# UD3c_bootstrap_output.net
KiCad netlist of a schematic drawn in Altium Designer
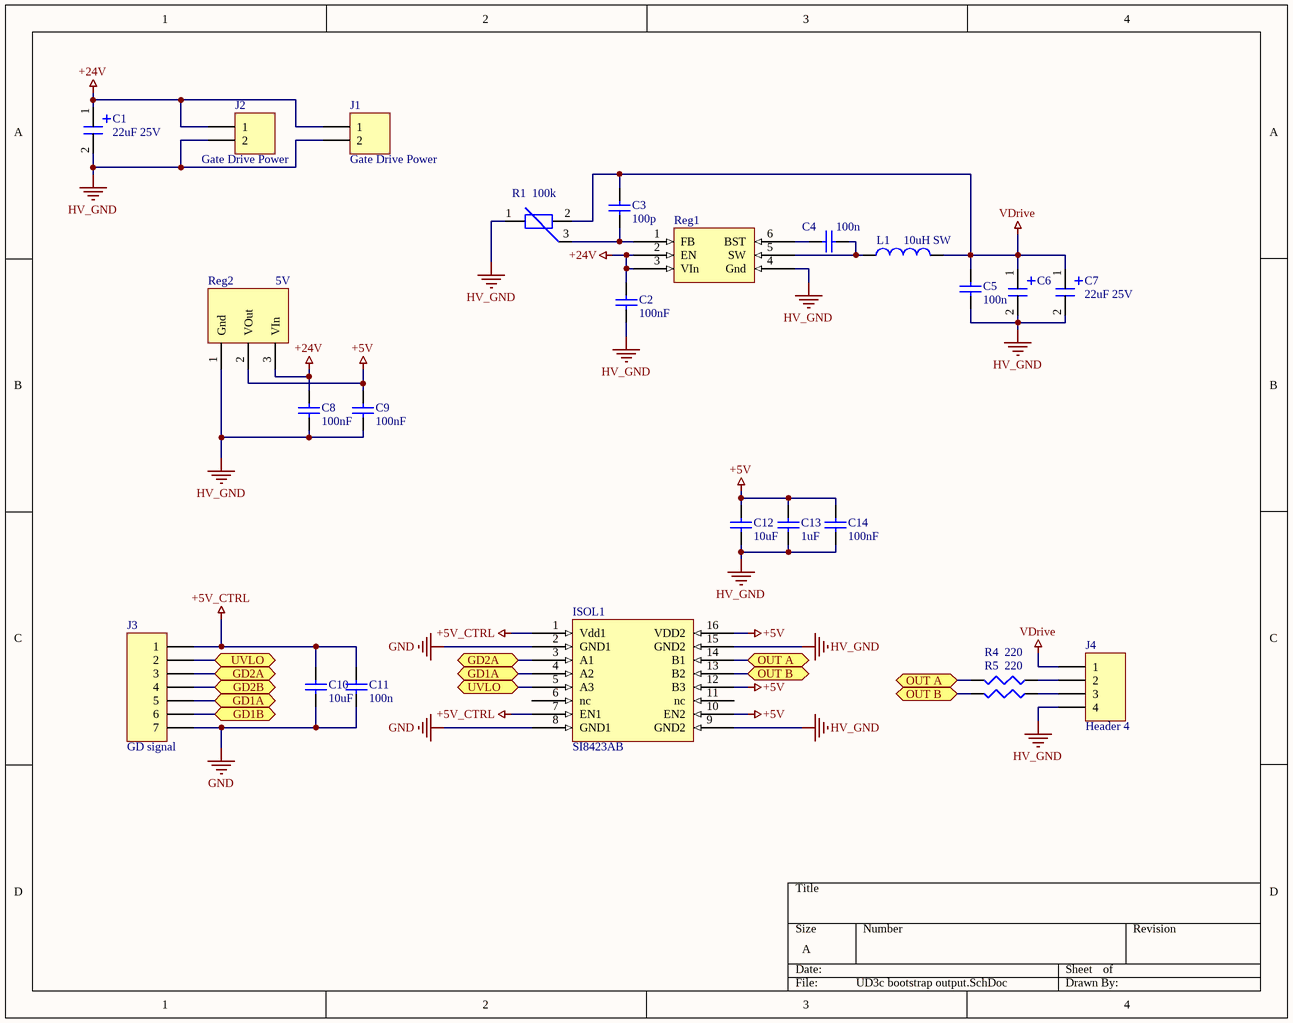
[diagram p0: UD3c bootstrap output.SchDoc]

(export (version "E")
  (design (tool "Eeschema 10.0.6"))
  (components
    (comp (ref "C1")
      (value "22uF 25V")
      (footprint "2917 Tantalum")
      (libsource (lib "stdLib") (part "Cap Polar"))
    )
    (comp (ref "C2") (value "100nF") (footprint "0603") (libsource (lib "stdLib") (part "Cap")))
    (comp (ref "C3") (value "100p") (footprint "0603") (libsource (lib "stdLib") (part "Cap")))
    (comp (ref "C4") (value "100n") (footprint "0603") (libsource (lib "stdLib") (part "Cap")))
    (comp (ref "C5") (value "100n") (footprint "0603") (libsource (lib "stdLib") (part "Cap")))
    (comp (ref "C6")
      (value "22uF 25V")
      (footprint "2917 Tantalum")
      (libsource (lib "stdLib") (part "Cap Polar"))
    )
    (comp (ref "C7")
      (value "22uF 25V")
      (footprint "2917 Tantalum")
      (libsource (lib "stdLib") (part "Cap Polar"))
    )
    (comp (ref "C8") (value "100nF") (footprint "0603") (libsource (lib "stdLib") (part "Cap")))
    (comp (ref "C9") (value "100nF") (footprint "0603") (libsource (lib "stdLib") (part "Cap")))
    (comp (ref "C10") (value "10uF") (footprint "0603") (libsource (lib "stdLib") (part "Cap")))
    (comp (ref "C11") (value "100n") (footprint "0603") (libsource (lib "stdLib") (part "Cap")))
    (comp (ref "C12") (value "10uF") (footprint "0603") (libsource (lib "stdLib") (part "Cap")))
    (comp (ref "C13") (value "1uF") (footprint "0603") (libsource (lib "stdLib") (part "Cap")))
    (comp (ref "C14") (value "100nF") (footprint "0603") (libsource (lib "stdLib") (part "Cap")))
    (comp (ref "ISOL1")
      (value "SI8423AB")
      (footprint "SOIC16 WIDE Isol")
      (description "Three (2/1) channel isolator")
      (libsource (lib "stdLib") (part "SI8423AB"))
    )
    (comp (ref "J1")
      (value "Gate Drive Power")
      (footprint "HDR1X2")
      (description "Header, 2-Pin")
      (fields (field (name "PUBLISHER") "Altium Limited"))
      (libsource (lib "Miscellaneous Connectors") (part "Header 2"))
    )
    (comp (ref "J2")
      (value "Gate Drive Power")
      (footprint "HDR1X2")
      (description "Header, 2-Pin")
      (fields (field (name "PUBLISHER") "Altium Limited"))
      (libsource (lib "Miscellaneous Connectors") (part "Header 2"))
    )
    (comp (ref "J3")
      (value "GD signal")
      (footprint "HDR1X7")
      (description "Header, 7-Pin")
      (fields (field (name "PUBLISHER") "Altium Limited"))
      (libsource (lib "Miscellaneous Connectors") (part "Header 7"))
    )
    (comp (ref "J4")
      (value "Header 4")
      (footprint "HDR1X4")
      (description "Header, 4-Pin")
      (fields (field (name "PUBLISHER") "Altium Limited"))
      (libsource (lib "Miscellaneous Connectors") (part "Header 4"))
    )
    (comp (ref "L1") (value "10uH SW") (footprint "1008") (libsource (lib "stdLib") (part "Inductor")))
    (comp (ref "R1") (value "100k") (footprint "Trimmer vert") (libsource (lib "stdLib") (part "Trimmer")))
    (comp (ref "R4") (value "220") (footprint "0603") (libsource (lib "stdLib") (part "Resistor")))
    (comp (ref "R5") (value "220") (footprint "0603") (libsource (lib "stdLib") (part "Resistor")))
    (comp (ref "Reg1")
      (value "Buck regulator")
      (footprint "TSOT26")
      (libsource (lib "stdLib") (part "AP6320"))
    )
    (comp (ref "Reg2") (value "5V") (footprint "SOT223") (libsource (lib "stdLib") (part "VReg")))
  )
  (nets
    (net (code "1") (name "+5V") (class "Default")
      (node (ref "C12") (pin "2") (pinfunction "2_2") (pintype "passive"))
      (node (ref "C13") (pin "2") (pinfunction "2_2") (pintype "passive"))
      (node (ref "C14") (pin "2") (pinfunction "2_2") (pintype "passive"))
      (node (ref "C9") (pin "2") (pinfunction "2_2") (pintype "passive"))
      (node (ref "ISOL1") (pin "10") (pinfunction "EN2_10") (pintype "input"))
      (node (ref "ISOL1") (pin "12") (pinfunction "B3_12") (pintype "input"))
      (node (ref "ISOL1") (pin "16") (pinfunction "VDD2_16") (pintype "input"))
      (node (ref "Reg2") (pin "2") (pinfunction "VOut_2") (pintype "passive"))
    )
    (net (code "2") (name "+5V_CTRL") (class "Default")
      (node (ref "C10") (pin "1") (pinfunction "1_1") (pintype "passive"))
      (node (ref "C11") (pin "1") (pinfunction "1_1") (pintype "passive"))
      (node (ref "ISOL1") (pin "1") (pinfunction "Vdd1_1") (pintype "input"))
      (node (ref "ISOL1") (pin "7") (pinfunction "EN1_7") (pintype "input"))
      (node (ref "J3") (pin "1") (pinfunction "1_1") (pintype "passive"))
    )
    (net (code "3") (name "+24V") (class "Default")
      (node (ref "C1") (pin "1") (pintype "passive"))
      (node (ref "C2") (pin "2") (pinfunction "2_2") (pintype "passive"))
      (node (ref "C8") (pin "2") (pinfunction "2_2") (pintype "passive"))
      (node (ref "J1") (pin "1") (pinfunction "1_1") (pintype "passive"))
      (node (ref "J2") (pin "1") (pinfunction "1_1") (pintype "passive"))
      (node (ref "Reg1") (pin "2") (pinfunction "EN_2") (pintype "input"))
      (node (ref "Reg1") (pin "3") (pinfunction "VIn_3") (pintype "input"))
      (node (ref "Reg2") (pin "3") (pinfunction "VIn_3") (pintype "passive"))
    )
    (net (code "4") (name "/GD1A") (class "Default")
      (node (ref "ISOL1") (pin "4") (pinfunction "A2_4") (pintype "input"))
      (node (ref "J3") (pin "5") (pinfunction "5_5") (pintype "passive"))
    )
    (net (code "5") (name "/GD1B") (class "Default")
      (node (ref "J3") (pin "6") (pinfunction "6_6") (pintype "passive"))
    )
    (net (code "6") (name "/GD2A") (class "Default")
      (node (ref "ISOL1") (pin "3") (pinfunction "A1_3") (pintype "input"))
      (node (ref "J3") (pin "3") (pinfunction "3_3") (pintype "passive"))
    )
    (net (code "7") (name "/GD2B") (class "Default")
      (node (ref "J3") (pin "4") (pinfunction "4_4") (pintype "passive"))
    )
    (net (code "8") (name "/OUT A") (class "Default")
      (node (ref "ISOL1") (pin "14") (pinfunction "B1_14") (pintype "input"))
      (node (ref "R4") (pin "2") (pinfunction "2_2") (pintype "passive"))
    )
    (net (code "9") (name "/OUT B") (class "Default")
      (node (ref "ISOL1") (pin "13") (pinfunction "B2_13") (pintype "input"))
      (node (ref "R5") (pin "2") (pinfunction "2_2") (pintype "passive"))
    )
    (net (code "10") (name "/UVLO") (class "Default")
      (node (ref "ISOL1") (pin "5") (pinfunction "A3_5") (pintype "input"))
      (node (ref "J3") (pin "2") (pinfunction "2_2") (pintype "passive"))
    )
    (net (code "11") (name "GND") (class "Default")
      (node (ref "C10") (pin "2") (pinfunction "2_2") (pintype "passive"))
      (node (ref "C11") (pin "2") (pinfunction "2_2") (pintype "passive"))
      (node (ref "ISOL1") (pin "2") (pinfunction "GND1_2") (pintype "input"))
      (node (ref "ISOL1") (pin "8") (pinfunction "GND1_8") (pintype "input"))
      (node (ref "J3") (pin "7") (pinfunction "7_7") (pintype "passive"))
    )
    (net (code "12") (name "HV_GND") (class "Default")
      (node (ref "C1") (pin "2") (pintype "passive"))
      (node (ref "C12") (pin "1") (pinfunction "1_1") (pintype "passive"))
      (node (ref "C13") (pin "1") (pinfunction "1_1") (pintype "passive"))
      (node (ref "C14") (pin "1") (pinfunction "1_1") (pintype "passive"))
      (node (ref "C2") (pin "1") (pinfunction "1_1") (pintype "passive"))
      (node (ref "C5") (pin "2") (pinfunction "2_2") (pintype "passive"))
      (node (ref "C6") (pin "2") (pintype "passive"))
      (node (ref "C7") (pin "2") (pintype "passive"))
      (node (ref "C8") (pin "1") (pinfunction "1_1") (pintype "passive"))
      (node (ref "C9") (pin "1") (pinfunction "1_1") (pintype "passive"))
      (node (ref "ISOL1") (pin "15") (pinfunction "GND2_15") (pintype "input"))
      (node (ref "ISOL1") (pin "9") (pinfunction "GND2_9") (pintype "input"))
      (node (ref "J1") (pin "2") (pinfunction "2_2") (pintype "passive"))
      (node (ref "J2") (pin "2") (pinfunction "2_2") (pintype "passive"))
      (node (ref "J4") (pin "4") (pinfunction "4_4") (pintype "passive"))
      (node (ref "R1") (pin "1") (pintype "passive"))
      (node (ref "Reg1") (pin "4") (pinfunction "Gnd_4") (pintype "input"))
      (node (ref "Reg2") (pin "1") (pinfunction "Gnd_1") (pintype "passive"))
    )
    (net (code "13") (name "Net-(J4-Pad2)") (class "Default")
      (node (ref "J4") (pin "2") (pinfunction "2_2") (pintype "passive"))
      (node (ref "R4") (pin "1") (pinfunction "1_1") (pintype "passive"))
    )
    (net (code "14") (name "Net-(J4-Pad3)") (class "Default")
      (node (ref "J4") (pin "3") (pinfunction "3_3") (pintype "passive"))
      (node (ref "R5") (pin "1") (pinfunction "1_1") (pintype "passive"))
    )
    (net (code "15") (name "Net-(Reg1-BST)") (class "Default")
      (node (ref "C4") (pin "1") (pinfunction "1_1") (pintype "passive"))
      (node (ref "Reg1") (pin "6") (pinfunction "BST_6") (pintype "input"))
    )
    (net (code "16") (name "Net-(Reg1-FB)") (class "Default")
      (node (ref "C3") (pin "1") (pinfunction "1_1") (pintype "passive"))
      (node (ref "R1") (pin "3") (pinfunction "3_3") (pintype "passive"))
      (node (ref "Reg1") (pin "1") (pinfunction "FB_1") (pintype "input"))
    )
    (net (code "17") (name "Net-(Reg1-SW)") (class "Default")
      (node (ref "C4") (pin "2") (pinfunction "2_2") (pintype "passive"))
      (node (ref "L1") (pin "1") (pinfunction "1_1") (pintype "passive"))
      (node (ref "Reg1") (pin "5") (pinfunction "SW_5") (pintype "input"))
    )
    (net (code "18") (name "VDrive") (class "Default")
      (node (ref "C3") (pin "2") (pinfunction "2_2") (pintype "passive"))
      (node (ref "C5") (pin "1") (pinfunction "1_1") (pintype "passive"))
      (node (ref "C6") (pin "1") (pintype "passive"))
      (node (ref "C7") (pin "1") (pintype "passive"))
      (node (ref "J4") (pin "1") (pinfunction "1_1") (pintype "passive"))
      (node (ref "L1") (pin "2") (pinfunction "2_2") (pintype "passive"))
      (node (ref "R1") (pin "2") (pintype "passive"))
    )
    (net (code "19") (name "unconnected-(ISOL1-nc-Pad6)") (class "Default")
      (node (ref "ISOL1") (pin "6") (pinfunction "nc_6") (pintype "input"))
    )
    (net (code "20") (name "unconnected-(ISOL1-nc-Pad11)") (class "Default")
      (node (ref "ISOL1") (pin "11") (pinfunction "nc_11") (pintype "input"))
    )
  )
)
